# DC24_HHV_RE-revp1.net
KiCad netlist of a schematic drawn in EAGLE
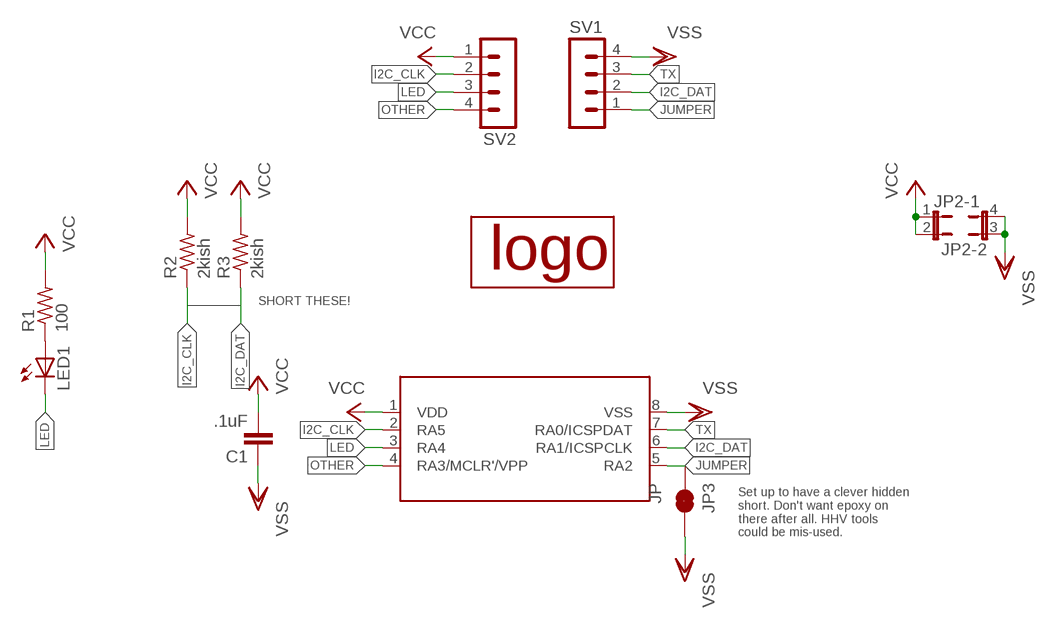
[diagram p0: schematic, sheet 1]

(export (version "E")
  (design (tool "Eeschema 10.0.6"))
  (components
    (comp (ref "C1")
      (value ".1uF")
      (footprint "eagle-import:C050-024X044")
      (libsource (lib "eagle-import") (part "C-EU050-024X044"))
    )
    (comp (ref "JP2")
      (value "JP2QE")
      (footprint "eagle-import:JP2Q")
      (libsource (lib "eagle-import") (part "JP2QE"))
    )
    (comp (ref "JP3")
      (value "JP")
      (footprint "eagle-import:PAD-JUMPER-2-NC_BY_TRACE_YES_SILK")
      (libsource (lib "eagle-import") (part "JUMPER-PAD-2-NC_BY_TRACE"))
    )
    (comp (ref "LED1")
      (value "LED5MM")
      (footprint "eagle-import:LED5MM")
      (libsource (lib "eagle-import") (part "LED5MM"))
    )
    (comp (ref "R1")
      (value "100")
      (footprint "eagle-import:0204_7")
      (libsource (lib "eagle-import") (part "R-US_0204/7"))
    )
    (comp (ref "R2")
      (value "2kish")
      (footprint "eagle-import:0204_7")
      (libsource (lib "eagle-import") (part "R-US_0204/7"))
    )
    (comp (ref "R3")
      (value "2kish")
      (footprint "eagle-import:0204_7")
      (libsource (lib "eagle-import") (part "R-US_0204/7"))
    )
    (comp (ref "SV1")
      (value "MA04-1")
      (footprint "eagle-import:MA04-1")
      (libsource (lib "eagle-import") (part "MA04-1"))
    )
    (comp (ref "SV2")
      (value "MA04-1")
      (footprint "eagle-import:MA04-1")
      (libsource (lib "eagle-import") (part "MA04-1"))
    )
    (comp (ref "U$1")
      (value "KBELOGO-SILK")
      (footprint "eagle-import:KBELOGO-SILK")
      (libsource (lib "eagle-import") (part "KBELOGO-SILK"))
    )
    (comp (ref "U1")
      (value "PIC12F1571")
      (footprint "eagle-import:DIL8")
      (libsource (lib "eagle-import") (part "PIC12F1571"))
    )
  )
  (nets
    (net (code "1") (name "I2C_CLK") (class "Default")
      (node (ref "R2") (pin "1") (pinfunction "1_1") (pintype "passive"))
      (node (ref "SV2") (pin "2") (pinfunction "2_2") (pintype "passive"))
      (node (ref "U1") (pin "2") (pinfunction "RA5_2") (pintype "bidirectional"))
    )
    (net (code "2") (name "I2C_DAT") (class "Default")
      (node (ref "R3") (pin "1") (pinfunction "1_1") (pintype "passive"))
      (node (ref "SV1") (pin "2") (pinfunction "2_2") (pintype "passive"))
      (node (ref "U1") (pin "6") (pinfunction "RA1/ICSPCLK_6") (pintype "bidirectional"))
    )
    (net (code "3") (name "JUMPER") (class "Default")
      (node (ref "JP3") (pin "1") (pinfunction "1_1") (pintype "passive"))
      (node (ref "SV1") (pin "1") (pinfunction "1_1") (pintype "passive"))
      (node (ref "U1") (pin "5") (pinfunction "RA2_5") (pintype "bidirectional"))
    )
    (net (code "4") (name "LED") (class "Default")
      (node (ref "LED1") (pin "K") (pinfunction "C_K") (pintype "passive"))
      (node (ref "SV2") (pin "3") (pinfunction "3_3") (pintype "passive"))
      (node (ref "U1") (pin "3") (pinfunction "RA4_3") (pintype "bidirectional"))
    )
    (net (code "5") (name "Net-(LED1-PadA)") (class "Default")
      (node (ref "LED1") (pin "A") (pinfunction "A_A") (pintype "passive"))
      (node (ref "R1") (pin "1") (pinfunction "1_1") (pintype "passive"))
    )
    (net (code "6") (name "OTHER") (class "Default")
      (node (ref "SV2") (pin "4") (pinfunction "4_4") (pintype "passive"))
      (node (ref "U1") (pin "4") (pinfunction "RA3/MCLR'/VPP_4") (pintype "bidirectional"))
    )
    (net (code "7") (name "TX") (class "Default")
      (node (ref "SV1") (pin "3") (pinfunction "3_3") (pintype "passive"))
      (node (ref "U1") (pin "7") (pinfunction "RA0/ICSPDAT_7") (pintype "bidirectional"))
    )
    (net (code "8") (name "VCC") (class "Default")
      (node (ref "C1") (pin "2") (pinfunction "2_2") (pintype "passive"))
      (node (ref "JP2") (pin "1") (pinfunction "1_1") (pintype "passive"))
      (node (ref "JP2") (pin "2") (pinfunction "2_2") (pintype "passive"))
      (node (ref "R1") (pin "2") (pinfunction "2_2") (pintype "passive"))
      (node (ref "R2") (pin "2") (pinfunction "2_2") (pintype "passive"))
      (node (ref "R3") (pin "2") (pinfunction "2_2") (pintype "passive"))
      (node (ref "SV2") (pin "1") (pinfunction "1_1") (pintype "passive"))
      (node (ref "U1") (pin "1") (pinfunction "VDD_1") (pintype "bidirectional"))
    )
    (net (code "9") (name "VSS") (class "Default")
      (node (ref "C1") (pin "1") (pinfunction "1_1") (pintype "passive"))
      (node (ref "JP2") (pin "3") (pinfunction "1_3") (pintype "passive"))
      (node (ref "JP2") (pin "4") (pinfunction "2_4") (pintype "passive"))
      (node (ref "JP3") (pin "2") (pinfunction "2_2") (pintype "passive"))
      (node (ref "SV1") (pin "4") (pinfunction "4_4") (pintype "passive"))
      (node (ref "U1") (pin "8") (pinfunction "VSS_8") (pintype "bidirectional"))
    )
  )
)
